# power_rf.net
KiCad netlist of a schematic drawn in Altium Designer
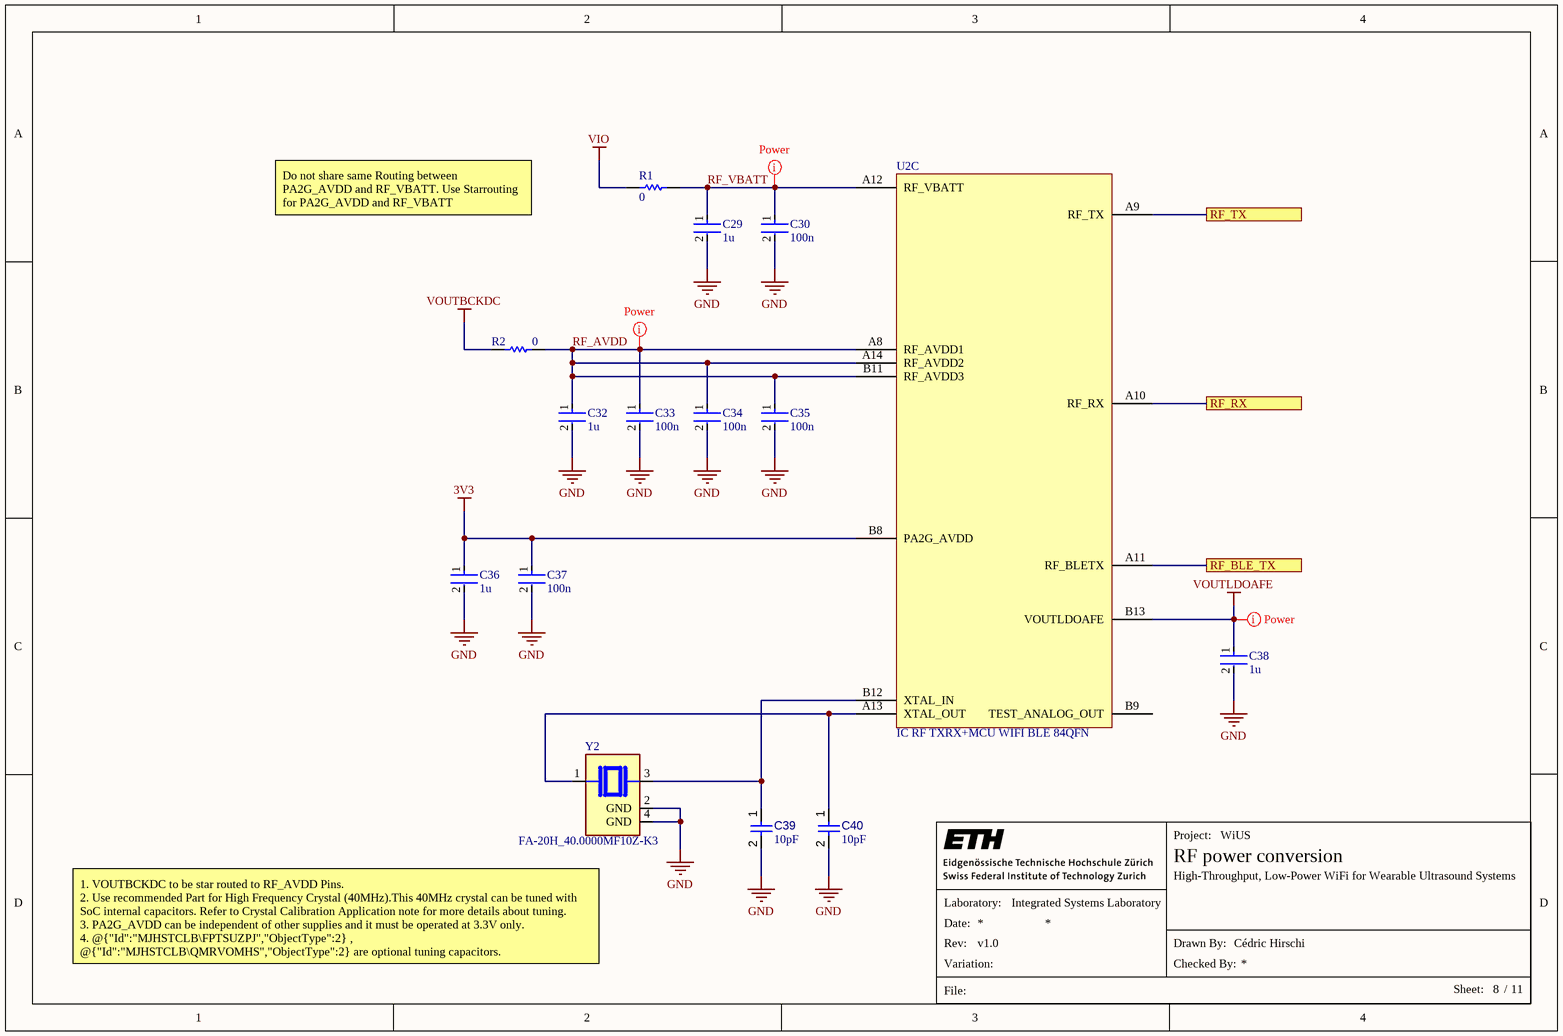
[diagram p0: power_rf.SchDoc]

(export (version "E")
  (design (tool "Eeschema 10.0.6"))
  (components
    (comp (ref "C29")
      (value "1u")
      (footprint "FP-GRM155-0_05-MFG")
      (description "Chip Multilayer Ceramic Capacitors for General Purpose, 0402, 1.0uF, X6S, 22%, 10%, 16V")
      (fields (field (name "TOLERANCE") "10%"))
      (libsource (lib "Altium Content Vault") (part "02cd4be3c70576c341d710602a673aa"))
    )
    (comp (ref "C30")
      (value "100n")
      (footprint "FP-GRT155-0_05-MFG")
      (description "Multi-Layer Ceramic Capacitor 100nF 50V X7R ±10% 0402 Paper T/R")
      (libsource (lib "Altium Content Vault") (part "02cd4be3c70576c341d710602a673aa"))
    )
    (comp (ref "C32")
      (value "1u")
      (footprint "FP-GRM155-0_05-MFG")
      (description "Chip Multilayer Ceramic Capacitors for General Purpose, 0402, 1.0uF, X6S, 22%, 10%, 16V")
      (fields (field (name "TOLERANCE") "10%"))
      (libsource (lib "Altium Content Vault") (part "02cd4be3c70576c341d710602a673aa"))
    )
    (comp (ref "C33")
      (value "100n")
      (footprint "FP-GRT155-0_05-MFG")
      (description "Multi-Layer Ceramic Capacitor 100nF 50V X7R ±10% 0402 Paper T/R")
      (libsource (lib "Altium Content Vault") (part "02cd4be3c70576c341d710602a673aa"))
    )
    (comp (ref "C34")
      (value "100n")
      (footprint "FP-GRT155-0_05-MFG")
      (description "Multi-Layer Ceramic Capacitor 100nF 50V X7R ±10% 0402 Paper T/R")
      (libsource (lib "Altium Content Vault") (part "02cd4be3c70576c341d710602a673aa"))
    )
    (comp (ref "C35")
      (value "100n")
      (footprint "FP-GRT155-0_05-MFG")
      (description "Multi-Layer Ceramic Capacitor 100nF 50V X7R ±10% 0402 Paper T/R")
      (libsource (lib "Altium Content Vault") (part "02cd4be3c70576c341d710602a673aa"))
    )
    (comp (ref "C36")
      (value "1u")
      (footprint "FP-GRM155-0_05-MFG")
      (description "Chip Multilayer Ceramic Capacitors for General Purpose, 0402, 1.0uF, X6S, 22%, 10%, 16V")
      (fields (field (name "TOLERANCE") "10%"))
      (libsource (lib "Altium Content Vault") (part "02cd4be3c70576c341d710602a673aa"))
    )
    (comp (ref "C37")
      (value "100n")
      (footprint "FP-GRT155-0_05-MFG")
      (description "Multi-Layer Ceramic Capacitor 100nF 50V X7R ±10% 0402 Paper T/R")
      (libsource (lib "Altium Content Vault") (part "02cd4be3c70576c341d710602a673aa"))
    )
    (comp (ref "C38")
      (value "1u")
      (footprint "FP-GRM155-0_05-MFG")
      (description "Chip Multilayer Ceramic Capacitors for General Purpose, 0402, 1.0uF, X6S, 22%, 10%, 16V")
      (fields (field (name "TOLERANCE") "10%"))
      (libsource (lib "Altium Content Vault") (part "02cd4be3c70576c341d710602a673aa"))
    )
    (comp (ref "C39")
      (value "10pF")
      (footprint "CAPC1005X55X30LL05T10")
      (description "Chip Capacitor, 10 pF, +/- 0.25 pF, 50 V, 0402 (1005 Metric)")
      (fields
        (field (name "TOLERANCE") "0.25%")
        (field (name "Comment") "Capacitor 10 pF +/- 0.25 pF 50 V 0402")
      )
      (libsource (lib "Cédric's Workspace") (part "CAP-NP-2"))
    )
    (comp (ref "C40")
      (value "10pF")
      (footprint "CAPC1005X55X30LL05T10")
      (description "Chip Capacitor, 10 pF, +/- 0.25 pF, 50 V, 0402 (1005 Metric)")
      (fields
        (field (name "TOLERANCE") "0.25%")
        (field (name "Comment") "Capacitor 10 pF +/- 0.25 pF 50 V 0402")
      )
      (libsource (lib "Cédric's Workspace") (part "CAP-NP-2"))
    )
    (comp (ref "R1")
      (value "0")
      (footprint "RESC1005X40X25ML05T10")
      (description "Chip Resistor, 0 Ohm, 0.063 W, -55 to 155 degC, 0402 (1005 Metric)")
      (fields (field (name "POWER") "63mW") (field (name "Comment") "Resistor 0R 0402 63 mW"))
      (libsource (lib "Cédric's Workspace") (part "RES-2"))
    )
    (comp (ref "R2")
      (value "0")
      (footprint "RESC1005X40X25ML05T10")
      (description "Chip Resistor, 0 Ohm, 0.063 W, -55 to 155 degC, 0402 (1005 Metric)")
      (fields (field (name "POWER") "63mW") (field (name "Comment") "Resistor 0R 0402 63 mW"))
      (libsource (lib "Cédric's Workspace") (part "RES-2"))
    )
    (comp (ref "U2")
      (value "IC RF TXRX+MCU WIFI BLE 84QFN")
      (footprint "wius:SIWG917M110LGTBA")
      (libsource (lib "wius") (part "SIWG917"))
    )
    (comp (ref "Y2")
      (value "FA-20H_40.0000MF10Z-K3")
      (footprint "FA-20H 40.0000MF10Z-K3:XTAL_FA-20H_40.0000MF10Z-K3")
      (fields (field (name "MF") "{'manufacturer': u'EPSON'}") (field (name "MP") "FA-20H 40.0000MF10Z-K3"))
      (libsource (lib "*") (part "FA-20H_40.0000MF10Z-K3"))
    )
  )
  (nets
    (net (code "1") (name "/RF_AVDD") (class "Default")
      (node (ref "C32") (pin "1") (pinfunction "1_1") (pintype "passive"))
      (node (ref "C33") (pin "1") (pinfunction "1_1") (pintype "passive"))
      (node (ref "C34") (pin "1") (pinfunction "1_1") (pintype "passive"))
      (node (ref "C35") (pin "1") (pinfunction "1_1") (pintype "passive"))
      (node (ref "R2") (pin "2") (pinfunction "2_2") (pintype "passive"))
      (node (ref "U2") (pin "A14") (pinfunction "RF_AVDD2_A14") (pintype "power_in"))
      (node (ref "U2") (pin "A8") (pinfunction "RF_AVDD1_A8") (pintype "power_in"))
      (node (ref "U2") (pin "B11") (pinfunction "RF_AVDD3_B11") (pintype "power_in"))
    )
    (net (code "2") (name "/RF_BLE_TX") (class "Default")
      (node (ref "U2") (pin "A11") (pinfunction "RF_BLETX_A11") (pintype "passive"))
    )
    (net (code "3") (name "/RF_RX") (class "Default")
      (node (ref "U2") (pin "A10") (pinfunction "RF_RX_A10") (pintype "passive"))
    )
    (net (code "4") (name "/RF_TX") (class "Default")
      (node (ref "U2") (pin "A9") (pinfunction "RF_TX_A9") (pintype "passive"))
    )
    (net (code "5") (name "/RF_VBATT") (class "Default")
      (node (ref "C29") (pin "1") (pinfunction "1_1") (pintype "passive"))
      (node (ref "C30") (pin "1") (pinfunction "1_1") (pintype "passive"))
      (node (ref "R1") (pin "2") (pinfunction "2_2") (pintype "passive"))
      (node (ref "U2") (pin "A12") (pinfunction "RF_VBATT_A12") (pintype "power_in"))
    )
    (net (code "6") (name "3V3") (class "Default")
      (node (ref "C36") (pin "1") (pinfunction "1_1") (pintype "passive"))
      (node (ref "C37") (pin "1") (pinfunction "1_1") (pintype "passive"))
      (node (ref "U2") (pin "B8") (pinfunction "PA2G_AVDD_B8") (pintype "power_in"))
    )
    (net (code "7") (name "GND") (class "Default")
      (node (ref "C29") (pin "2") (pinfunction "2_2") (pintype "passive"))
      (node (ref "C30") (pin "2") (pinfunction "2_2") (pintype "passive"))
      (node (ref "C32") (pin "2") (pinfunction "2_2") (pintype "passive"))
      (node (ref "C33") (pin "2") (pinfunction "2_2") (pintype "passive"))
      (node (ref "C34") (pin "2") (pinfunction "2_2") (pintype "passive"))
      (node (ref "C35") (pin "2") (pinfunction "2_2") (pintype "passive"))
      (node (ref "C36") (pin "2") (pinfunction "2_2") (pintype "passive"))
      (node (ref "C37") (pin "2") (pinfunction "2_2") (pintype "passive"))
      (node (ref "C38") (pin "2") (pinfunction "2_2") (pintype "passive"))
      (node (ref "C39") (pin "2") (pinfunction "2_2") (pintype "passive"))
      (node (ref "C40") (pin "2") (pinfunction "2_2") (pintype "passive"))
      (node (ref "Y2") (pin "2") (pinfunction "GND_2") (pintype "power_in"))
      (node (ref "Y2") (pin "4") (pinfunction "GND_4") (pintype "power_in"))
    )
    (net (code "8") (name "Net-(U2C-XTAL_IN)") (class "Default")
      (node (ref "C39") (pin "1") (pinfunction "1_1") (pintype "passive"))
      (node (ref "U2") (pin "B12") (pinfunction "XTAL_IN_B12") (pintype "passive"))
      (node (ref "Y2") (pin "3") (pinfunction "2_3") (pintype "passive"))
    )
    (net (code "9") (name "Net-(U2C-XTAL_OUT)") (class "Default")
      (node (ref "C40") (pin "1") (pinfunction "1_1") (pintype "passive"))
      (node (ref "U2") (pin "A13") (pinfunction "XTAL_OUT_A13") (pintype "passive"))
      (node (ref "Y2") (pin "1") (pinfunction "1_1") (pintype "passive"))
    )
    (net (code "10") (name "VIO") (class "Default")
      (node (ref "R1") (pin "1") (pinfunction "1_1") (pintype "passive"))
    )
    (net (code "11") (name "VOUTBCKDC") (class "Default")
      (node (ref "R2") (pin "1") (pinfunction "1_1") (pintype "passive"))
    )
    (net (code "12") (name "VOUTLDOAFE") (class "Default")
      (node (ref "C38") (pin "1") (pinfunction "1_1") (pintype "passive"))
      (node (ref "U2") (pin "B13") (pinfunction "VOUTLDOAFE_B13") (pintype "power_in"))
    )
    (net (code "13") (name "unconnected-(U2C-TEST_ANALOG_OUT-PadB9)") (class "Default")
      (node (ref "U2") (pin "B9") (pinfunction "TEST_ANALOG_OUT_B9") (pintype "passive"))
    )
  )
)
